# LED_Interface.net
KiCad netlist of a schematic drawn in Altium Designer
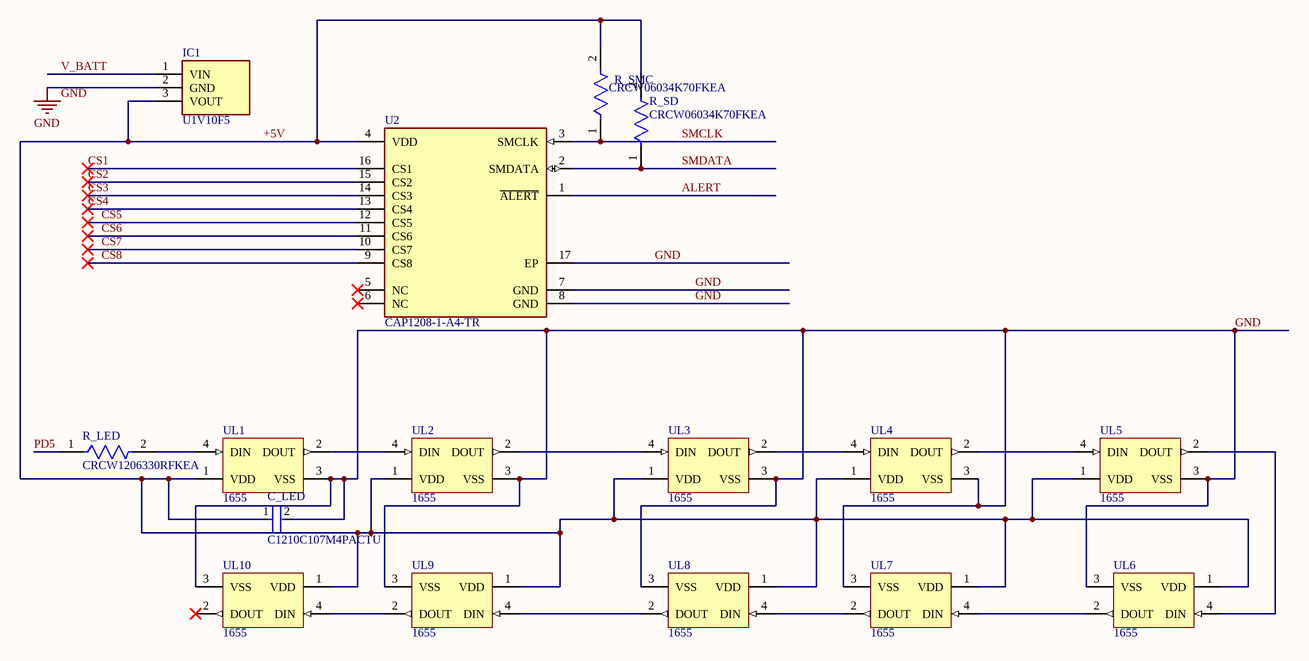
[diagram p0: LED_Interface.SchDoc]

(export (version "E")
  (design (tool "Eeschema 10.0.6"))
  (components
    (comp (ref "C_LED")
      (value "C1210C107M4PACTU")
      (footprint "FP-C1210C-FS-MFG")
      (description "CAP CER 100UF 16V X5R 1210")
      (fields (field (name "TOLERANCE") "20%"))
      (libsource (lib "Altium Content Vault") (part "02cd4be3c70576c341d710602a673aa"))
    )
    (comp (ref "IC1")
      (value "U1V10F5")
      (footprint "SamacSys:U1V10F5")
      (description "Integrated Circuit")
      (libsource (lib "*") (part "U1V10F5"))
    )
    (comp (ref "R_LED")
      (value "CRCW1206330RFKEA")
      (footprint "FP-CRCW1206-e3-IPC_A")
      (description "RES Thick Film, 330Ω, 1%, 0.25W, 100ppm/°C, 1206")
      (fields (field (name "TOLERANCE") "1%"))
      (libsource (lib "Altium Content Vault") (part "1029c3af85768c4190bb7ad29bc67b5"))
    )
    (comp (ref "R_SD")
      (value "CRCW06034K70FKEA")
      (footprint "FP-CRCW0603-e3-IPC_A")
      (description "RES Thick Film, 4.7kΩ, 1%, 0.1W, 100ppm/°C, 0603")
      (fields (field (name "TOLERANCE") "1%"))
      (libsource (lib "Altium Content Vault") (part "1029c3af85768c4190bb7ad29bc67b5"))
    )
    (comp (ref "R_SMC")
      (value "CRCW06034K70FKEA")
      (footprint "FP-CRCW0603-e3-IPC_A")
      (description "RES Thick Film, 4.7kΩ, 1%, 0.1W, 100ppm/°C, 0603")
      (fields (field (name "TOLERANCE") "1%"))
      (libsource (lib "Altium Content Vault") (part "1029c3af85768c4190bb7ad29bc67b5"))
    )
    (comp (ref "U2")
      (value "CAP1208-1-A4-TR")
      (footprint "FP-CAP1208-1-A4-TR-MFG")
      (description "IC TOUCH SENSOR CAP 8CH 16QFN")
      (libsource (lib "Altium Content Vault") (part "9b5987f98370c0deff87ba428a4e129"))
    )
    (comp (ref "UL1")
      (value "1655")
      (footprint "ADA-RGB-1655_V")
      (fields (field (name "MANUFACTURER") "Adafruit-Industries-LLC"))
      (libsource (lib "Altium Content Vault") (part "ADA-RGB-1655-4"))
    )
    (comp (ref "UL2")
      (value "1655")
      (footprint "ADA-RGB-1655_V")
      (fields (field (name "MANUFACTURER") "Adafruit-Industries-LLC"))
      (libsource (lib "Altium Content Vault") (part "ADA-RGB-1655-4"))
    )
    (comp (ref "UL3")
      (value "1655")
      (footprint "ADA-RGB-1655_V")
      (fields (field (name "MANUFACTURER") "Adafruit-Industries-LLC"))
      (libsource (lib "Altium Content Vault") (part "ADA-RGB-1655-4"))
    )
    (comp (ref "UL4")
      (value "1655")
      (footprint "ADA-RGB-1655_V")
      (fields (field (name "MANUFACTURER") "Adafruit-Industries-LLC"))
      (libsource (lib "Altium Content Vault") (part "ADA-RGB-1655-4"))
    )
    (comp (ref "UL5")
      (value "1655")
      (footprint "ADA-RGB-1655_V")
      (fields (field (name "MANUFACTURER") "Adafruit-Industries-LLC"))
      (libsource (lib "Altium Content Vault") (part "ADA-RGB-1655-4"))
    )
    (comp (ref "UL6")
      (value "1655")
      (footprint "ADA-RGB-1655_V")
      (fields (field (name "MANUFACTURER") "Adafruit-Industries-LLC"))
      (libsource (lib "") (part "ADA-RGB-1655-4_1"))
    )
    (comp (ref "UL7")
      (value "1655")
      (footprint "ADA-RGB-1655_V")
      (fields (field (name "MANUFACTURER") "Adafruit-Industries-LLC"))
      (libsource (lib "") (part "ADA-RGB-1655-4_1"))
    )
    (comp (ref "UL8")
      (value "1655")
      (footprint "ADA-RGB-1655_V")
      (fields (field (name "MANUFACTURER") "Adafruit-Industries-LLC"))
      (libsource (lib "") (part "ADA-RGB-1655-4_1"))
    )
    (comp (ref "UL9")
      (value "1655")
      (footprint "ADA-RGB-1655_V")
      (fields (field (name "MANUFACTURER") "Adafruit-Industries-LLC"))
      (libsource (lib "") (part "ADA-RGB-1655-4_1"))
    )
    (comp (ref "UL10")
      (value "1655")
      (footprint "ADA-RGB-1655_V")
      (fields (field (name "MANUFACTURER") "Adafruit-Industries-LLC"))
      (libsource (lib "") (part "ADA-RGB-1655-4_1"))
    )
  )
  (nets
    (net (code "1") (name "/+5V") (class "Default")
      (node (ref "C_LED") (pin "1") (pinfunction "1_1") (pintype "passive"))
      (node (ref "IC1") (pin "3") (pinfunction "VOUT_3") (pintype "passive"))
      (node (ref "R_SD") (pin "2") (pinfunction "2_2") (pintype "passive"))
      (node (ref "R_SMC") (pin "2") (pinfunction "2_2") (pintype "passive"))
      (node (ref "U2") (pin "4") (pinfunction "VDD_4") (pintype "power_in"))
      (node (ref "UL1") (pin "1") (pinfunction "VDD_1") (pintype "power_in"))
      (node (ref "UL10") (pin "1") (pinfunction "VDD_1") (pintype "power_in"))
      (node (ref "UL2") (pin "1") (pinfunction "VDD_1") (pintype "power_in"))
      (node (ref "UL3") (pin "1") (pinfunction "VDD_1") (pintype "power_in"))
      (node (ref "UL4") (pin "1") (pinfunction "VDD_1") (pintype "power_in"))
      (node (ref "UL5") (pin "1") (pinfunction "VDD_1") (pintype "power_in"))
      (node (ref "UL6") (pin "1") (pinfunction "VDD_1") (pintype "power_in"))
      (node (ref "UL7") (pin "1") (pinfunction "VDD_1") (pintype "power_in"))
      (node (ref "UL8") (pin "1") (pinfunction "VDD_1") (pintype "power_in"))
      (node (ref "UL9") (pin "1") (pinfunction "VDD_1") (pintype "power_in"))
    )
    (net (code "2") (name "/ALERT") (class "Default")
      (node (ref "U2") (pin "1") (pinfunction "~{ALERT}_1") (pintype "passive"))
    )
    (net (code "3") (name "/CS1") (class "Default")
      (node (ref "U2") (pin "16") (pinfunction "CS1_16") (pintype "passive+no_connect"))
    )
    (net (code "4") (name "/CS2") (class "Default")
      (node (ref "U2") (pin "15") (pinfunction "CS2_15") (pintype "passive+no_connect"))
    )
    (net (code "5") (name "/CS3") (class "Default")
      (node (ref "U2") (pin "14") (pinfunction "CS3_14") (pintype "passive+no_connect"))
    )
    (net (code "6") (name "/CS4") (class "Default")
      (node (ref "U2") (pin "13") (pinfunction "CS4_13") (pintype "passive+no_connect"))
    )
    (net (code "7") (name "/CS5") (class "Default")
      (node (ref "U2") (pin "12") (pinfunction "CS5_12") (pintype "passive+no_connect"))
    )
    (net (code "8") (name "/CS6") (class "Default")
      (node (ref "U2") (pin "11") (pinfunction "CS6_11") (pintype "passive+no_connect"))
    )
    (net (code "9") (name "/CS7") (class "Default")
      (node (ref "U2") (pin "10") (pinfunction "CS7_10") (pintype "passive+no_connect"))
    )
    (net (code "10") (name "/CS8") (class "Default")
      (node (ref "U2") (pin "9") (pinfunction "CS8_9") (pintype "passive+no_connect"))
    )
    (net (code "11") (name "/PD5") (class "Default")
      (node (ref "R_LED") (pin "1") (pinfunction "1_1") (pintype "passive"))
    )
    (net (code "12") (name "/SMCLK") (class "Default")
      (node (ref "R_SMC") (pin "1") (pinfunction "1_1") (pintype "passive"))
      (node (ref "U2") (pin "3") (pinfunction "SMCLK_3") (pintype "input"))
    )
    (net (code "13") (name "/SMDATA") (class "Default")
      (node (ref "R_SD") (pin "1") (pinfunction "1_1") (pintype "passive"))
      (node (ref "U2") (pin "2") (pinfunction "SMDATA_2") (pintype "bidirectional"))
    )
    (net (code "14") (name "/V_BATT") (class "Default")
      (node (ref "IC1") (pin "1") (pinfunction "VIN_1") (pintype "passive"))
    )
    (net (code "15") (name "GND") (class "Default")
      (node (ref "C_LED") (pin "2") (pinfunction "2_2") (pintype "passive"))
      (node (ref "IC1") (pin "2") (pinfunction "GND_2") (pintype "passive"))
      (node (ref "U2") (pin "17") (pinfunction "EP_17") (pintype "power_in"))
      (node (ref "U2") (pin "7") (pinfunction "GND_7") (pintype "power_in"))
      (node (ref "U2") (pin "8") (pinfunction "GND_8") (pintype "power_in"))
      (node (ref "UL1") (pin "3") (pinfunction "VSS_3") (pintype "power_in"))
      (node (ref "UL10") (pin "3") (pinfunction "VSS_3") (pintype "power_in"))
      (node (ref "UL2") (pin "3") (pinfunction "VSS_3") (pintype "power_in"))
      (node (ref "UL3") (pin "3") (pinfunction "VSS_3") (pintype "power_in"))
      (node (ref "UL4") (pin "3") (pinfunction "VSS_3") (pintype "power_in"))
      (node (ref "UL5") (pin "3") (pinfunction "VSS_3") (pintype "power_in"))
      (node (ref "UL6") (pin "3") (pinfunction "VSS_3") (pintype "power_in"))
      (node (ref "UL7") (pin "3") (pinfunction "VSS_3") (pintype "power_in"))
      (node (ref "UL8") (pin "3") (pinfunction "VSS_3") (pintype "power_in"))
      (node (ref "UL9") (pin "3") (pinfunction "VSS_3") (pintype "power_in"))
    )
    (net (code "16") (name "Net-(UL1-DIN)") (class "Default")
      (node (ref "R_LED") (pin "2") (pinfunction "2_2") (pintype "passive"))
      (node (ref "UL1") (pin "4") (pinfunction "DIN_4") (pintype "input"))
    )
    (net (code "17") (name "Net-(UL1-DOUT)") (class "Default")
      (node (ref "UL1") (pin "2") (pinfunction "DOUT_2") (pintype "output"))
      (node (ref "UL2") (pin "4") (pinfunction "DIN_4") (pintype "input"))
    )
    (net (code "18") (name "Net-(UL2-DOUT)") (class "Default")
      (node (ref "UL2") (pin "2") (pinfunction "DOUT_2") (pintype "output"))
      (node (ref "UL3") (pin "4") (pinfunction "DIN_4") (pintype "input"))
    )
    (net (code "19") (name "Net-(UL3-DOUT)") (class "Default")
      (node (ref "UL3") (pin "2") (pinfunction "DOUT_2") (pintype "output"))
      (node (ref "UL4") (pin "4") (pinfunction "DIN_4") (pintype "input"))
    )
    (net (code "20") (name "Net-(UL4-DOUT)") (class "Default")
      (node (ref "UL4") (pin "2") (pinfunction "DOUT_2") (pintype "output"))
      (node (ref "UL5") (pin "4") (pinfunction "DIN_4") (pintype "input"))
    )
    (net (code "21") (name "Net-(UL5-DOUT)") (class "Default")
      (node (ref "UL5") (pin "2") (pinfunction "DOUT_2") (pintype "output"))
      (node (ref "UL6") (pin "4") (pinfunction "DIN_4") (pintype "input"))
    )
    (net (code "22") (name "Net-(UL6-DOUT)") (class "Default")
      (node (ref "UL6") (pin "2") (pinfunction "DOUT_2") (pintype "output"))
      (node (ref "UL7") (pin "4") (pinfunction "DIN_4") (pintype "input"))
    )
    (net (code "23") (name "Net-(UL7-DOUT)") (class "Default")
      (node (ref "UL7") (pin "2") (pinfunction "DOUT_2") (pintype "output"))
      (node (ref "UL8") (pin "4") (pinfunction "DIN_4") (pintype "input"))
    )
    (net (code "24") (name "Net-(UL8-DOUT)") (class "Default")
      (node (ref "UL8") (pin "2") (pinfunction "DOUT_2") (pintype "output"))
      (node (ref "UL9") (pin "4") (pinfunction "DIN_4") (pintype "input"))
    )
    (net (code "25") (name "Net-(UL10-DIN)") (class "Default")
      (node (ref "UL10") (pin "4") (pinfunction "DIN_4") (pintype "input"))
      (node (ref "UL9") (pin "2") (pinfunction "DOUT_2") (pintype "output"))
    )
    (net (code "26") (name "unconnected-(U2-NC-Pad5)") (class "Default")
      (node (ref "U2") (pin "5") (pinfunction "NC_5") (pintype "passive+no_connect"))
    )
    (net (code "27") (name "unconnected-(U2-NC-Pad6)") (class "Default")
      (node (ref "U2") (pin "6") (pinfunction "NC_6") (pintype "passive+no_connect"))
    )
    (net (code "28") (name "unconnected-(UL10-DOUT-Pad2)") (class "Default")
      (node (ref "UL10") (pin "2") (pinfunction "DOUT_2") (pintype "output+no_connect"))
    )
  )
)
